# mcf51jm128vlh.net
KiCad netlist of a schematic drawn in Altium Designer
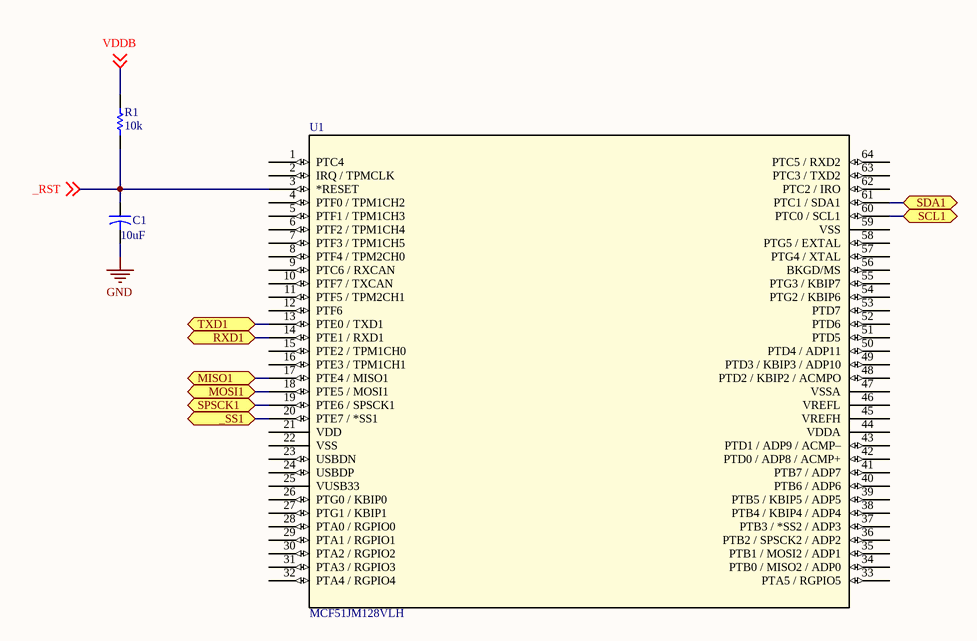
[diagram p0: mcf51jm128vlh.SchDoc]

(export (version "E")
  (design (tool "Eeschema 10.0.6"))
  (components
    (comp (ref "C1")
      (value "10uF")
      (footprint "CAPR5-4X5")
      (description "Capacitor")
      (fields (field (name "Comment") "Cap2") (field (name "PUBLISHER") "Altium Limited"))
      (libsource (lib "Miscellaneous Devices") (part "Cap2"))
    )
    (comp (ref "R1")
      (value "10k")
      (footprint "AXIAL-0.3")
      (description "Resistor")
      (fields (field (name "Comment") "Res1") (field (name "PUBLISHER") "Altium Limited"))
      (libsource (lib "Miscellaneous Devices") (part "Res1"))
    )
    (comp (ref "U1")
      (value "MCF51JM128VLH")
      (footprint "QFP64_FRE")
      (description "No Description Available")
      (libsource (lib "MCF51JM128VLH") (part "MCF51JM128VLH"))
    )
  )
  (nets
    (net (code "1") (name "/MISO1") (class "Default")
      (node (ref "U1") (pin "17") (pinfunction "PTE4_/_MISO1_17") (pintype "bidirectional"))
    )
    (net (code "2") (name "/MOSI1") (class "Default")
      (node (ref "U1") (pin "18") (pinfunction "PTE5_/_MOSI1_18") (pintype "bidirectional"))
    )
    (net (code "3") (name "/RXD1") (class "Default")
      (node (ref "U1") (pin "14") (pinfunction "PTE1_/_RXD1_14") (pintype "bidirectional"))
    )
    (net (code "4") (name "/SCL1") (class "Default")
      (node (ref "U1") (pin "60") (pinfunction "PTC0_/_SCL1_60") (pintype "bidirectional"))
    )
    (net (code "5") (name "/SDA1") (class "Default")
      (node (ref "U1") (pin "61") (pinfunction "PTC1_/_SDA1_61") (pintype "bidirectional"))
    )
    (net (code "6") (name "/SPSCK1") (class "Default")
      (node (ref "U1") (pin "19") (pinfunction "PTE6_/_SPSCK1_19") (pintype "bidirectional"))
    )
    (net (code "7") (name "/TXD1") (class "Default")
      (node (ref "U1") (pin "13") (pinfunction "PTE0_/_TXD1_13") (pintype "bidirectional"))
    )
    (net (code "8") (name "/_SS1") (class "Default")
      (node (ref "U1") (pin "20") (pinfunction "PTE7_/_*SS1_20") (pintype "bidirectional"))
    )
    (net (code "9") (name "GND") (class "Default")
      (node (ref "C1") (pin "2") (pinfunction "2_2") (pintype "passive"))
    )
    (net (code "10") (name "VDDB") (class "Default")
      (node (ref "R1") (pin "2") (pinfunction "2_2") (pintype "passive"))
    )
    (net (code "11") (name "_RST") (class "Default")
      (node (ref "C1") (pin "1") (pinfunction "1_1") (pintype "passive"))
      (node (ref "R1") (pin "1") (pinfunction "1_1") (pintype "passive"))
      (node (ref "U1") (pin "3") (pinfunction "*RESET_3") (pintype "bidirectional"))
    )
    (net (code "12") (name "unconnected-(U1-BKGD{slash}MS-Pad56)") (class "Default")
      (node (ref "U1") (pin "56") (pinfunction "BKGD/MS_56") (pintype "bidirectional"))
    )
    (net (code "13") (name "unconnected-(U1-IRQ_{slash}_TPMCLK-Pad2)") (class "Default")
      (node (ref "U1") (pin "2") (pinfunction "IRQ_/_TPMCLK_2") (pintype "bidirectional"))
    )
    (net (code "14") (name "unconnected-(U1-PTA0_{slash}_RGPIO0-Pad28)") (class "Default")
      (node (ref "U1") (pin "28") (pinfunction "PTA0_/_RGPIO0_28") (pintype "bidirectional"))
    )
    (net (code "15") (name "unconnected-(U1-PTA1_{slash}_RGPIO1-Pad29)") (class "Default")
      (node (ref "U1") (pin "29") (pinfunction "PTA1_/_RGPIO1_29") (pintype "bidirectional"))
    )
    (net (code "16") (name "unconnected-(U1-PTA2_{slash}_RGPIO2-Pad30)") (class "Default")
      (node (ref "U1") (pin "30") (pinfunction "PTA2_/_RGPIO2_30") (pintype "bidirectional"))
    )
    (net (code "17") (name "unconnected-(U1-PTA3_{slash}_RGPIO3-Pad31)") (class "Default")
      (node (ref "U1") (pin "31") (pinfunction "PTA3_/_RGPIO3_31") (pintype "bidirectional"))
    )
    (net (code "18") (name "unconnected-(U1-PTA4_{slash}_RGPIO4-Pad32)") (class "Default")
      (node (ref "U1") (pin "32") (pinfunction "PTA4_/_RGPIO4_32") (pintype "bidirectional"))
    )
    (net (code "19") (name "unconnected-(U1-PTA5_{slash}_RGPIO5-Pad33)") (class "Default")
      (node (ref "U1") (pin "33") (pinfunction "PTA5_/_RGPIO5_33") (pintype "bidirectional"))
    )
    (net (code "20") (name "unconnected-(U1-PTB0_{slash}_MISO2_{slash}_ADP0-Pad34)") (class "Default")
      (node (ref "U1") (pin "34") (pinfunction "PTB0_/_MISO2_/_ADP0_34") (pintype "bidirectional"))
    )
    (net (code "21") (name "unconnected-(U1-PTB1_{slash}_MOSI2_{slash}_ADP1-Pad35)") (class "Default")
      (node (ref "U1") (pin "35") (pinfunction "PTB1_/_MOSI2_/_ADP1_35") (pintype "bidirectional"))
    )
    (net (code "22") (name "unconnected-(U1-PTB2_{slash}_SPSCK2_{slash}_ADP2-Pad36)") (class "Default")
      (node (ref "U1") (pin "36") (pinfunction "PTB2_/_SPSCK2_/_ADP2_36") (pintype "bidirectional"))
    )
    (net (code "23") (name "unconnected-(U1-PTB3_{slash}_*SS2_{slash}_ADP3-Pad37)") (class "Default")
      (node (ref "U1") (pin "37") (pinfunction "PTB3_/_*SS2_/_ADP3_37") (pintype "bidirectional"))
    )
    (net (code "24") (name "unconnected-(U1-PTB4_{slash}_KBIP4_{slash}_ADP4-Pad38)") (class "Default")
      (node (ref "U1") (pin "38") (pinfunction "PTB4_/_KBIP4_/_ADP4_38") (pintype "bidirectional"))
    )
    (net (code "25") (name "unconnected-(U1-PTB5_{slash}_KBIP5_{slash}_ADP5-Pad39)") (class "Default")
      (node (ref "U1") (pin "39") (pinfunction "PTB5_/_KBIP5_/_ADP5_39") (pintype "bidirectional"))
    )
    (net (code "26") (name "unconnected-(U1-PTB6_{slash}_ADP6-Pad40)") (class "Default")
      (node (ref "U1") (pin "40") (pinfunction "PTB6_/_ADP6_40") (pintype "bidirectional"))
    )
    (net (code "27") (name "unconnected-(U1-PTB7_{slash}_ADP7-Pad41)") (class "Default")
      (node (ref "U1") (pin "41") (pinfunction "PTB7_/_ADP7_41") (pintype "bidirectional"))
    )
    (net (code "28") (name "unconnected-(U1-PTC2_{slash}_IRO-Pad62)") (class "Default")
      (node (ref "U1") (pin "62") (pinfunction "PTC2_/_IRO_62") (pintype "bidirectional"))
    )
    (net (code "29") (name "unconnected-(U1-PTC3_{slash}_TXD2-Pad63)") (class "Default")
      (node (ref "U1") (pin "63") (pinfunction "PTC3_/_TXD2_63") (pintype "bidirectional"))
    )
    (net (code "30") (name "unconnected-(U1-PTC4-Pad1)") (class "Default")
      (node (ref "U1") (pin "1") (pinfunction "PTC4_1") (pintype "bidirectional"))
    )
    (net (code "31") (name "unconnected-(U1-PTC5_{slash}_RXD2-Pad64)") (class "Default")
      (node (ref "U1") (pin "64") (pinfunction "PTC5_/_RXD2_64") (pintype "bidirectional"))
    )
    (net (code "32") (name "unconnected-(U1-PTC6_{slash}_RXCAN-Pad9)") (class "Default")
      (node (ref "U1") (pin "9") (pinfunction "PTC6_/_RXCAN_9") (pintype "bidirectional"))
    )
    (net (code "33") (name "unconnected-(U1-PTD0_{slash}_ADP8_{slash}_ACMP+-Pad42)") (class "Default")
      (node (ref "U1") (pin "42") (pinfunction "PTD0_/_ADP8_/_ACMP+_42") (pintype "bidirectional"))
    )
    (net (code "34") (name "unconnected-(U1-PTD1_{slash}_ADP9_{slash}_ACMP–-Pad43)") (class "Default")
      (node (ref "U1") (pin "43") (pinfunction "PTD1_/_ADP9_/_ACMP–_43") (pintype "bidirectional"))
    )
    (net (code "35") (name "unconnected-(U1-PTD2_{slash}_KBIP2_{slash}_ACMPO-Pad48)") (class "Default")
      (node (ref "U1") (pin "48") (pinfunction "PTD2_/_KBIP2_/_ACMPO_48") (pintype "bidirectional"))
    )
    (net (code "36") (name "unconnected-(U1-PTD3_{slash}_KBIP3_{slash}_ADP10-Pad49)") (class "Default")
      (node (ref "U1") (pin "49") (pinfunction "PTD3_/_KBIP3_/_ADP10_49") (pintype "bidirectional"))
    )
    (net (code "37") (name "unconnected-(U1-PTD4_{slash}_ADP11-Pad50)") (class "Default")
      (node (ref "U1") (pin "50") (pinfunction "PTD4_/_ADP11_50") (pintype "bidirectional"))
    )
    (net (code "38") (name "unconnected-(U1-PTD5-Pad51)") (class "Default")
      (node (ref "U1") (pin "51") (pinfunction "PTD5_51") (pintype "bidirectional"))
    )
    (net (code "39") (name "unconnected-(U1-PTD6-Pad52)") (class "Default")
      (node (ref "U1") (pin "52") (pinfunction "PTD6_52") (pintype "bidirectional"))
    )
    (net (code "40") (name "unconnected-(U1-PTD7-Pad53)") (class "Default")
      (node (ref "U1") (pin "53") (pinfunction "PTD7_53") (pintype "bidirectional"))
    )
    (net (code "41") (name "unconnected-(U1-PTE2_{slash}_TPM1CH0-Pad15)") (class "Default")
      (node (ref "U1") (pin "15") (pinfunction "PTE2_/_TPM1CH0_15") (pintype "bidirectional"))
    )
    (net (code "42") (name "unconnected-(U1-PTE3_{slash}_TPM1CH1-Pad16)") (class "Default")
      (node (ref "U1") (pin "16") (pinfunction "PTE3_/_TPM1CH1_16") (pintype "bidirectional"))
    )
    (net (code "43") (name "unconnected-(U1-PTF0_{slash}_TPM1CH2-Pad4)") (class "Default")
      (node (ref "U1") (pin "4") (pinfunction "PTF0_/_TPM1CH2_4") (pintype "bidirectional"))
    )
    (net (code "44") (name "unconnected-(U1-PTF1_{slash}_TPM1CH3-Pad5)") (class "Default")
      (node (ref "U1") (pin "5") (pinfunction "PTF1_/_TPM1CH3_5") (pintype "bidirectional"))
    )
    (net (code "45") (name "unconnected-(U1-PTF2_{slash}_TPM1CH4-Pad6)") (class "Default")
      (node (ref "U1") (pin "6") (pinfunction "PTF2_/_TPM1CH4_6") (pintype "bidirectional"))
    )
    (net (code "46") (name "unconnected-(U1-PTF3_{slash}_TPM1CH5-Pad7)") (class "Default")
      (node (ref "U1") (pin "7") (pinfunction "PTF3_/_TPM1CH5_7") (pintype "bidirectional"))
    )
    (net (code "47") (name "unconnected-(U1-PTF4_{slash}_TPM2CH0-Pad8)") (class "Default")
      (node (ref "U1") (pin "8") (pinfunction "PTF4_/_TPM2CH0_8") (pintype "bidirectional"))
    )
    (net (code "48") (name "unconnected-(U1-PTF5_{slash}_TPM2CH1-Pad11)") (class "Default")
      (node (ref "U1") (pin "11") (pinfunction "PTF5_/_TPM2CH1_11") (pintype "bidirectional"))
    )
    (net (code "49") (name "unconnected-(U1-PTF6-Pad12)") (class "Default")
      (node (ref "U1") (pin "12") (pinfunction "PTF6_12") (pintype "bidirectional"))
    )
    (net (code "50") (name "unconnected-(U1-PTF7_{slash}_TXCAN-Pad10)") (class "Default")
      (node (ref "U1") (pin "10") (pinfunction "PTF7_/_TXCAN_10") (pintype "bidirectional"))
    )
    (net (code "51") (name "unconnected-(U1-PTG0_{slash}_KBIP0-Pad26)") (class "Default")
      (node (ref "U1") (pin "26") (pinfunction "PTG0_/_KBIP0_26") (pintype "bidirectional"))
    )
    (net (code "52") (name "unconnected-(U1-PTG1_{slash}_KBIP1-Pad27)") (class "Default")
      (node (ref "U1") (pin "27") (pinfunction "PTG1_/_KBIP1_27") (pintype "bidirectional"))
    )
    (net (code "53") (name "unconnected-(U1-PTG2_{slash}_KBIP6-Pad54)") (class "Default")
      (node (ref "U1") (pin "54") (pinfunction "PTG2_/_KBIP6_54") (pintype "bidirectional"))
    )
    (net (code "54") (name "unconnected-(U1-PTG3_{slash}_KBIP7-Pad55)") (class "Default")
      (node (ref "U1") (pin "55") (pinfunction "PTG3_/_KBIP7_55") (pintype "bidirectional"))
    )
    (net (code "55") (name "unconnected-(U1-PTG4_{slash}_XTAL-Pad57)") (class "Default")
      (node (ref "U1") (pin "57") (pinfunction "PTG4_/_XTAL_57") (pintype "bidirectional"))
    )
    (net (code "56") (name "unconnected-(U1-PTG5_{slash}_EXTAL-Pad58)") (class "Default")
      (node (ref "U1") (pin "58") (pinfunction "PTG5_/_EXTAL_58") (pintype "bidirectional"))
    )
    (net (code "57") (name "unconnected-(U1-USBDN-Pad23)") (class "Default")
      (node (ref "U1") (pin "23") (pinfunction "USBDN_23") (pintype "bidirectional"))
    )
    (net (code "58") (name "unconnected-(U1-USBDP-Pad24)") (class "Default")
      (node (ref "U1") (pin "24") (pinfunction "USBDP_24") (pintype "bidirectional"))
    )
    (net (code "59") (name "unconnected-(U1-VDD-Pad21)") (class "Default")
      (node (ref "U1") (pin "21") (pinfunction "VDD_21") (pintype "power_in"))
    )
    (net (code "60") (name "unconnected-(U1-VDDA-Pad44)") (class "Default")
      (node (ref "U1") (pin "44") (pinfunction "VDDA_44") (pintype "power_in"))
    )
    (net (code "61") (name "unconnected-(U1-VREFH-Pad45)") (class "Default")
      (node (ref "U1") (pin "45") (pinfunction "VREFH_45") (pintype "power_in"))
    )
    (net (code "62") (name "unconnected-(U1-VREFL-Pad46)") (class "Default")
      (node (ref "U1") (pin "46") (pinfunction "VREFL_46") (pintype "power_in"))
    )
    (net (code "63") (name "unconnected-(U1-VSS-Pad22)") (class "Default")
      (node (ref "U1") (pin "22") (pinfunction "VSS_22") (pintype "power_in"))
    )
    (net (code "64") (name "unconnected-(U1-VSS-Pad59)") (class "Default")
      (node (ref "U1") (pin "59") (pinfunction "VSS_59") (pintype "power_in"))
    )
    (net (code "65") (name "unconnected-(U1-VSSA-Pad47)") (class "Default")
      (node (ref "U1") (pin "47") (pinfunction "VSSA_47") (pintype "power_in"))
    )
    (net (code "66") (name "unconnected-(U1-VUSB33-Pad25)") (class "Default")
      (node (ref "U1") (pin "25") (pinfunction "VUSB33_25") (pintype "power_in"))
    )
  )
)
